# Programmer.net
KiCad netlist of a schematic drawn in Altium Designer
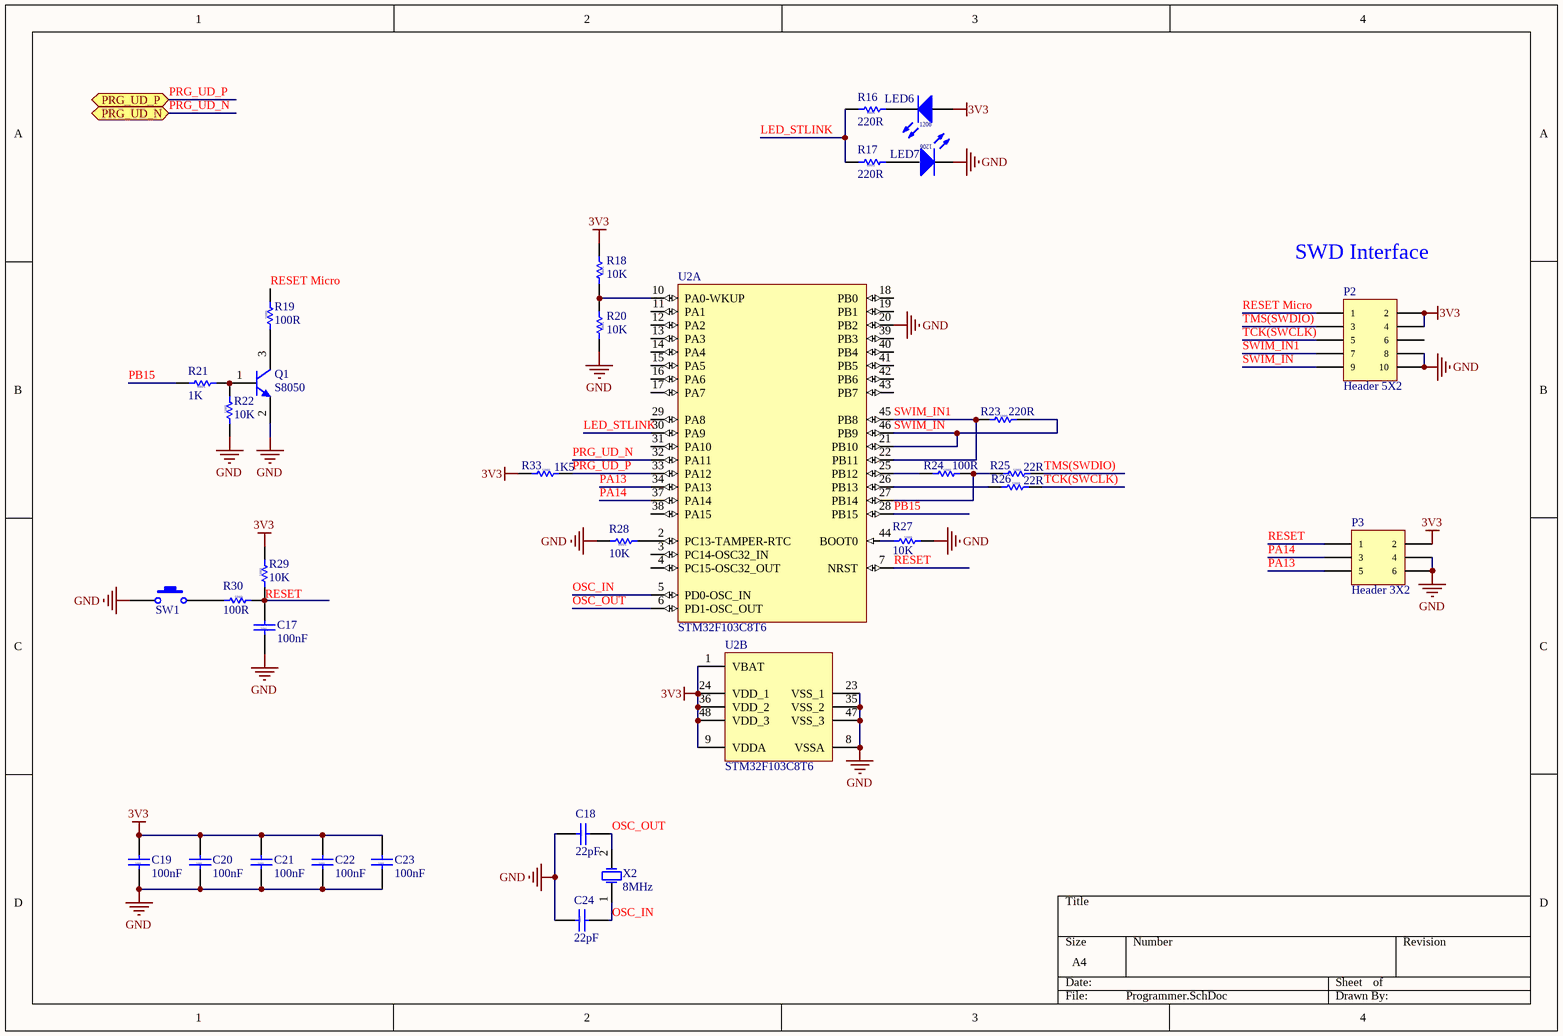
[diagram p0: Programmer.SchDoc]

(export (version "E")
  (design (tool "Eeschema 10.0.6"))
  (components
    (comp (ref "C17")
      (value "100nF")
      (footprint "RES 0805")
      (libsource (lib "Full lib F.kh-V2") (part "CAP 0805"))
    )
    (comp (ref "C18")
      (value "22pF")
      (footprint "RES 0805")
      (libsource (lib "Full lib F.kh-V2") (part "CAP 0805"))
    )
    (comp (ref "C19")
      (value "100nF")
      (footprint "RES 0805")
      (libsource (lib "Full lib F.kh-V2") (part "CAP 0805"))
    )
    (comp (ref "C20")
      (value "100nF")
      (footprint "RES 0805")
      (libsource (lib "Full lib F.kh-V2") (part "CAP 0805"))
    )
    (comp (ref "C21")
      (value "100nF")
      (footprint "RES 0805")
      (libsource (lib "Full lib F.kh-V2") (part "CAP 0805"))
    )
    (comp (ref "C22")
      (value "100nF")
      (footprint "RES 0805")
      (libsource (lib "Full lib F.kh-V2") (part "CAP 0805"))
    )
    (comp (ref "C23")
      (value "100nF")
      (footprint "RES 0805")
      (libsource (lib "Full lib F.kh-V2") (part "CAP 0805"))
    )
    (comp (ref "C24")
      (value "22pF")
      (footprint "RES 0805")
      (libsource (lib "Full lib F.kh-V2") (part "CAP 0805"))
    )
    (comp (ref "LED6")
      (value "LED 1206")
      (footprint "LED 1206")
      (libsource (lib "Full lib F.kh-V2") (part "LED 1206"))
    )
    (comp (ref "LED7")
      (value "LED 1206")
      (footprint "LED 1206")
      (libsource (lib "Full lib F.kh-V2") (part "LED 1206"))
    )
    (comp (ref "P2")
      (value "Header 5X2")
      (footprint "HDR2X5")
      (description "Header, 5-Pin, Dual row")
      (fields (field (name "PUBLISHER") "Altium Limited"))
      (libsource (lib "Full lib F.kh-V2") (part "Header 5X2"))
    )
    (comp (ref "P3")
      (value "Header 3X2")
      (footprint "HDR2X3")
      (description "Header, 3-Pin, Dual row")
      (fields (field (name "PUBLISHER") "Altium Limited"))
      (libsource (lib "Full lib F.kh-V2") (part "Header 3X2"))
    )
    (comp (ref "Q1")
      (value "S8050")
      (footprint "SOT-23")
      (libsource (lib "Full lib F.kh-V2") (part "S8050 SMD"))
    )
    (comp (ref "R16")
      (value "220R")
      (footprint "RES 0805")
      (libsource (lib "Full lib F.kh-V2") (part "RES 0805"))
    )
    (comp (ref "R17")
      (value "220R")
      (footprint "RES 0805")
      (libsource (lib "Full lib F.kh-V2") (part "RES 0805"))
    )
    (comp (ref "R18")
      (value "10K")
      (footprint "RES 0805")
      (libsource (lib "Full lib F.kh-V2") (part "RES 0805"))
    )
    (comp (ref "R19")
      (value "100R")
      (footprint "RES 0805")
      (libsource (lib "Full lib F.kh-V2") (part "RES 0805"))
    )
    (comp (ref "R20")
      (value "10K")
      (footprint "RES 0805")
      (libsource (lib "Full lib F.kh-V2") (part "RES 0805"))
    )
    (comp (ref "R21")
      (value "1K")
      (footprint "RES 0805")
      (libsource (lib "Full lib F.kh-V2") (part "RES 0805"))
    )
    (comp (ref "R22")
      (value "10K")
      (footprint "RES 0805")
      (libsource (lib "Full lib F.kh-V2") (part "RES 0805"))
    )
    (comp (ref "R23")
      (value "220R")
      (footprint "RES 0805")
      (libsource (lib "Full lib F.kh-V2") (part "RES 0805"))
    )
    (comp (ref "R24")
      (value "100R")
      (footprint "RES 0805")
      (libsource (lib "Full lib F.kh-V2") (part "RES 0805"))
    )
    (comp (ref "R25")
      (value "22R")
      (footprint "RES 0805")
      (libsource (lib "Full lib F.kh-V2") (part "RES 0805"))
    )
    (comp (ref "R26")
      (value "22R")
      (footprint "RES 0805")
      (libsource (lib "Full lib F.kh-V2") (part "RES 0805"))
    )
    (comp (ref "R27")
      (value "10K")
      (footprint "RES 0805")
      (libsource (lib "Full lib F.kh-V2") (part "RES 0805"))
    )
    (comp (ref "R28")
      (value "10K")
      (footprint "RES 0805")
      (libsource (lib "Full lib F.kh-V2") (part "RES 0805"))
    )
    (comp (ref "R29")
      (value "10K")
      (footprint "RES 0805")
      (libsource (lib "Full lib F.kh-V2") (part "RES 0805"))
    )
    (comp (ref "R30")
      (value "100R")
      (footprint "RES 0805")
      (libsource (lib "Full lib F.kh-V2") (part "RES 0805"))
    )
    (comp (ref "R33")
      (value "1K5")
      (footprint "RES 0805")
      (libsource (lib "Full lib F.kh-V2") (part "RES 0805"))
    )
    (comp (ref "SW1")
      (value "Pushing Switch")
      (footprint "micro sch")
      (fields (field (name "PUBLISHER") "Altium Limited"))
      (libsource (lib "Full lib F.kh-V2") (part "Pushing Switch 2Pin"))
    )
    (comp (ref "U2")
      (value "STM32F103C8T6")
      (footprint "STM-LQFP48_N")
      (libsource (lib "STMicroelectronics STM32 F1") (part "STM32F103C8T6"))
    )
    (comp (ref "X2")
      (value "8MHz")
      (footprint "XTAL - SMD")
      (libsource (lib "Full lib F.kh-V2") (part "XTAL - SMD"))
    )
  )
  (nets
    (net (code "1") (name "/LED_STLINK") (class "Default")
      (node (ref "R16") (pin "2") (pinfunction "2_2") (pintype "passive"))
      (node (ref "R17") (pin "2") (pinfunction "2_2") (pintype "passive"))
      (node (ref "U2") (pin "30") (pinfunction "PA9_30") (pintype "bidirectional"))
    )
    (net (code "2") (name "/OSC_IN") (class "Default")
      (node (ref "C24") (pin "2") (pinfunction "2_2") (pintype "passive"))
      (node (ref "U2") (pin "5") (pinfunction "PD0-OSC_IN_5") (pintype "bidirectional"))
      (node (ref "X2") (pin "1") (pinfunction "OSC1_1") (pintype "passive"))
    )
    (net (code "3") (name "/OSC_OUT") (class "Default")
      (node (ref "C18") (pin "2") (pinfunction "2_2") (pintype "passive"))
      (node (ref "U2") (pin "6") (pinfunction "PD1-OSC_OUT_6") (pintype "bidirectional"))
      (node (ref "X2") (pin "2") (pinfunction "OSC2_2") (pintype "passive"))
    )
    (net (code "4") (name "/PA13") (class "Default")
      (node (ref "P3") (pin "5") (pinfunction "5_5") (pintype "passive"))
      (node (ref "U2") (pin "34") (pinfunction "PA13_34") (pintype "bidirectional"))
    )
    (net (code "5") (name "/PA14") (class "Default")
      (node (ref "P3") (pin "3") (pinfunction "3_3") (pintype "passive"))
      (node (ref "U2") (pin "37") (pinfunction "PA14_37") (pintype "bidirectional"))
    )
    (net (code "6") (name "/PB15") (class "Default")
      (node (ref "R21") (pin "2") (pinfunction "2_2") (pintype "passive"))
      (node (ref "U2") (pin "28") (pinfunction "PB15_28") (pintype "bidirectional"))
    )
    (net (code "7") (name "/PRG_UD_N") (class "Default")
      (node (ref "U2") (pin "32") (pinfunction "PA11_32") (pintype "bidirectional"))
    )
    (net (code "8") (name "/PRG_UD_P") (class "Default")
      (node (ref "R33") (pin "2") (pinfunction "2_2") (pintype "passive"))
      (node (ref "U2") (pin "33") (pinfunction "PA12_33") (pintype "bidirectional"))
    )
    (net (code "9") (name "/RESET") (class "Default")
      (node (ref "C17") (pin "2") (pinfunction "2_2") (pintype "passive"))
      (node (ref "P3") (pin "1") (pinfunction "1_1") (pintype "passive"))
      (node (ref "R29") (pin "1") (pinfunction "1_1") (pintype "passive"))
      (node (ref "R30") (pin "2") (pinfunction "2_2") (pintype "passive"))
      (node (ref "U2") (pin "7") (pinfunction "NRST_7") (pintype "bidirectional"))
    )
    (net (code "10") (name "/RESET Micro") (class "Default")
      (node (ref "P2") (pin "1") (pinfunction "1_1") (pintype "passive"))
      (node (ref "R19") (pin "2") (pinfunction "2_2") (pintype "passive"))
    )
    (net (code "11") (name "/SWIM_IN") (class "Default")
      (node (ref "P2") (pin "9") (pinfunction "9_9") (pintype "passive"))
      (node (ref "R23") (pin "2") (pinfunction "2_2") (pintype "passive"))
      (node (ref "U2") (pin "21") (pinfunction "PB10_21") (pintype "bidirectional"))
      (node (ref "U2") (pin "46") (pinfunction "PB9_46") (pintype "bidirectional"))
    )
    (net (code "12") (name "/SWIM_IN1") (class "Default")
      (node (ref "P2") (pin "7") (pinfunction "7_7") (pintype "passive"))
      (node (ref "R23") (pin "1") (pinfunction "1_1") (pintype "passive"))
      (node (ref "U2") (pin "22") (pinfunction "PB11_22") (pintype "bidirectional"))
      (node (ref "U2") (pin "45") (pinfunction "PB8_45") (pintype "bidirectional"))
    )
    (net (code "13") (name "/TCK(SWCLK)") (class "Default")
      (node (ref "P2") (pin "5") (pinfunction "5_5") (pintype "passive"))
      (node (ref "R26") (pin "2") (pinfunction "2_2") (pintype "passive"))
    )
    (net (code "14") (name "/TMS(SWDIO)") (class "Default")
      (node (ref "P2") (pin "3") (pinfunction "3_3") (pintype "passive"))
      (node (ref "R25") (pin "2") (pinfunction "2_2") (pintype "passive"))
    )
    (net (code "15") (name "3V3") (class "Default")
      (node (ref "C19") (pin "2") (pinfunction "2_2") (pintype "passive"))
      (node (ref "C20") (pin "2") (pinfunction "2_2") (pintype "passive"))
      (node (ref "C21") (pin "2") (pinfunction "2_2") (pintype "passive"))
      (node (ref "C22") (pin "2") (pinfunction "2_2") (pintype "passive"))
      (node (ref "C23") (pin "2") (pinfunction "2_2") (pintype "passive"))
      (node (ref "LED6") (pin "1") (pinfunction "A_1") (pintype "passive"))
      (node (ref "P2") (pin "2") (pinfunction "2_2") (pintype "passive"))
      (node (ref "P2") (pin "4") (pinfunction "4_4") (pintype "passive"))
      (node (ref "P3") (pin "2") (pinfunction "2_2") (pintype "passive"))
      (node (ref "R18") (pin "1") (pinfunction "1_1") (pintype "passive"))
      (node (ref "R29") (pin "2") (pinfunction "2_2") (pintype "passive"))
      (node (ref "R33") (pin "1") (pinfunction "1_1") (pintype "passive"))
      (node (ref "U2") (pin "1") (pinfunction "VBAT_1") (pintype "power_in"))
      (node (ref "U2") (pin "24") (pinfunction "VDD_1_24") (pintype "power_in"))
      (node (ref "U2") (pin "36") (pinfunction "VDD_2_36") (pintype "power_in"))
      (node (ref "U2") (pin "48") (pinfunction "VDD_3_48") (pintype "power_in"))
      (node (ref "U2") (pin "9") (pinfunction "VDDA_9") (pintype "power_in"))
    )
    (net (code "16") (name "GND") (class "Default")
      (node (ref "C17") (pin "1") (pinfunction "1_1") (pintype "passive"))
      (node (ref "C18") (pin "1") (pinfunction "1_1") (pintype "passive"))
      (node (ref "C19") (pin "1") (pinfunction "1_1") (pintype "passive"))
      (node (ref "C20") (pin "1") (pinfunction "1_1") (pintype "passive"))
      (node (ref "C21") (pin "1") (pinfunction "1_1") (pintype "passive"))
      (node (ref "C22") (pin "1") (pinfunction "1_1") (pintype "passive"))
      (node (ref "C23") (pin "1") (pinfunction "1_1") (pintype "passive"))
      (node (ref "C24") (pin "1") (pinfunction "1_1") (pintype "passive"))
      (node (ref "LED7") (pin "2") (pinfunction "K_2") (pintype "passive"))
      (node (ref "P2") (pin "10") (pinfunction "10_10") (pintype "passive"))
      (node (ref "P2") (pin "8") (pinfunction "8_8") (pintype "passive"))
      (node (ref "P3") (pin "4") (pinfunction "4_4") (pintype "passive"))
      (node (ref "P3") (pin "6") (pinfunction "6_6") (pintype "passive"))
      (node (ref "Q1") (pin "2") (pinfunction "E_2") (pintype "passive"))
      (node (ref "R20") (pin "2") (pinfunction "2_2") (pintype "passive"))
      (node (ref "R22") (pin "1") (pinfunction "1_1") (pintype "passive"))
      (node (ref "R27") (pin "2") (pinfunction "2_2") (pintype "passive"))
      (node (ref "R28") (pin "2") (pinfunction "2_2") (pintype "passive"))
      (node (ref "SW1") (pin "1") (pinfunction "1_1") (pintype "passive"))
      (node (ref "U2") (pin "20") (pinfunction "PB2_20") (pintype "bidirectional"))
      (node (ref "U2") (pin "23") (pinfunction "VSS_1_23") (pintype "power_in"))
      (node (ref "U2") (pin "35") (pinfunction "VSS_2_35") (pintype "power_in"))
      (node (ref "U2") (pin "47") (pinfunction "VSS_3_47") (pintype "power_in"))
      (node (ref "U2") (pin "8") (pinfunction "VSSA_8") (pintype "power_in"))
    )
    (net (code "17") (name "Net-(LED6-K)") (class "Default")
      (node (ref "LED6") (pin "2") (pinfunction "K_2") (pintype "passive"))
      (node (ref "R16") (pin "1") (pinfunction "1_1") (pintype "passive"))
    )
    (net (code "18") (name "Net-(LED7-A)") (class "Default")
      (node (ref "LED7") (pin "1") (pinfunction "A_1") (pintype "passive"))
      (node (ref "R17") (pin "1") (pinfunction "1_1") (pintype "passive"))
    )
    (net (code "19") (name "Net-(Q1-B)") (class "Default")
      (node (ref "Q1") (pin "1") (pinfunction "B_1") (pintype "passive"))
      (node (ref "R21") (pin "1") (pinfunction "1_1") (pintype "passive"))
      (node (ref "R22") (pin "2") (pinfunction "2_2") (pintype "passive"))
    )
    (net (code "20") (name "Net-(Q1-C)") (class "Default")
      (node (ref "Q1") (pin "3") (pinfunction "C_3") (pintype "passive"))
      (node (ref "R19") (pin "1") (pinfunction "1_1") (pintype "passive"))
    )
    (net (code "21") (name "Net-(R30-Pad1)") (class "Default")
      (node (ref "R30") (pin "1") (pinfunction "1_1") (pintype "passive"))
      (node (ref "SW1") (pin "2") (pinfunction "2_2") (pintype "passive"))
    )
    (net (code "22") (name "Net-(U2A-BOOT0)") (class "Default")
      (node (ref "R27") (pin "1") (pinfunction "1_1") (pintype "passive"))
      (node (ref "U2") (pin "44") (pinfunction "BOOT0_44") (pintype "input"))
    )
    (net (code "23") (name "Net-(U2A-PA0-WKUP)") (class "Default")
      (node (ref "R18") (pin "2") (pinfunction "2_2") (pintype "passive"))
      (node (ref "R20") (pin "1") (pinfunction "1_1") (pintype "passive"))
      (node (ref "U2") (pin "10") (pinfunction "PA0-WKUP_10") (pintype "bidirectional"))
    )
    (net (code "24") (name "Net-(U2A-PB12)") (class "Default")
      (node (ref "R24") (pin "1") (pinfunction "1_1") (pintype "passive"))
      (node (ref "U2") (pin "25") (pinfunction "PB12_25") (pintype "bidirectional"))
    )
    (net (code "25") (name "Net-(U2A-PB13)") (class "Default")
      (node (ref "R26") (pin "1") (pinfunction "1_1") (pintype "passive"))
      (node (ref "U2") (pin "26") (pinfunction "PB13_26") (pintype "bidirectional"))
    )
    (net (code "26") (name "Net-(U2A-PB14)") (class "Default")
      (node (ref "R24") (pin "2") (pinfunction "2_2") (pintype "passive"))
      (node (ref "R25") (pin "1") (pinfunction "1_1") (pintype "passive"))
      (node (ref "U2") (pin "27") (pinfunction "PB14_27") (pintype "bidirectional"))
    )
    (net (code "27") (name "Net-(U2A-PC13-TAMPER-RTC)") (class "Default")
      (node (ref "R28") (pin "1") (pinfunction "1_1") (pintype "passive"))
      (node (ref "U2") (pin "2") (pinfunction "PC13-TAMPER-RTC_2") (pintype "bidirectional"))
    )
    (net (code "28") (name "unconnected-(P2-Pad6)") (class "Default")
      (node (ref "P2") (pin "6") (pinfunction "6_6") (pintype "passive"))
    )
    (net (code "29") (name "unconnected-(U2A-PA1-Pad11)") (class "Default")
      (node (ref "U2") (pin "11") (pinfunction "PA1_11") (pintype "bidirectional"))
    )
    (net (code "30") (name "unconnected-(U2A-PA2-Pad12)") (class "Default")
      (node (ref "U2") (pin "12") (pinfunction "PA2_12") (pintype "bidirectional"))
    )
    (net (code "31") (name "unconnected-(U2A-PA3-Pad13)") (class "Default")
      (node (ref "U2") (pin "13") (pinfunction "PA3_13") (pintype "bidirectional"))
    )
    (net (code "32") (name "unconnected-(U2A-PA4-Pad14)") (class "Default")
      (node (ref "U2") (pin "14") (pinfunction "PA4_14") (pintype "bidirectional"))
    )
    (net (code "33") (name "unconnected-(U2A-PA5-Pad15)") (class "Default")
      (node (ref "U2") (pin "15") (pinfunction "PA5_15") (pintype "bidirectional"))
    )
    (net (code "34") (name "unconnected-(U2A-PA6-Pad16)") (class "Default")
      (node (ref "U2") (pin "16") (pinfunction "PA6_16") (pintype "bidirectional"))
    )
    (net (code "35") (name "unconnected-(U2A-PA7-Pad17)") (class "Default")
      (node (ref "U2") (pin "17") (pinfunction "PA7_17") (pintype "bidirectional"))
    )
    (net (code "36") (name "unconnected-(U2A-PA8-Pad29)") (class "Default")
      (node (ref "U2") (pin "29") (pinfunction "PA8_29") (pintype "bidirectional"))
    )
    (net (code "37") (name "unconnected-(U2A-PA10-Pad31)") (class "Default")
      (node (ref "U2") (pin "31") (pinfunction "PA10_31") (pintype "bidirectional"))
    )
    (net (code "38") (name "unconnected-(U2A-PA15-Pad38)") (class "Default")
      (node (ref "U2") (pin "38") (pinfunction "PA15_38") (pintype "bidirectional"))
    )
    (net (code "39") (name "unconnected-(U2A-PB0-Pad18)") (class "Default")
      (node (ref "U2") (pin "18") (pinfunction "PB0_18") (pintype "bidirectional"))
    )
    (net (code "40") (name "unconnected-(U2A-PB1-Pad19)") (class "Default")
      (node (ref "U2") (pin "19") (pinfunction "PB1_19") (pintype "bidirectional"))
    )
    (net (code "41") (name "unconnected-(U2A-PB3-Pad39)") (class "Default")
      (node (ref "U2") (pin "39") (pinfunction "PB3_39") (pintype "bidirectional"))
    )
    (net (code "42") (name "unconnected-(U2A-PB4-Pad40)") (class "Default")
      (node (ref "U2") (pin "40") (pinfunction "PB4_40") (pintype "bidirectional"))
    )
    (net (code "43") (name "unconnected-(U2A-PB5-Pad41)") (class "Default")
      (node (ref "U2") (pin "41") (pinfunction "PB5_41") (pintype "bidirectional"))
    )
    (net (code "44") (name "unconnected-(U2A-PB6-Pad42)") (class "Default")
      (node (ref "U2") (pin "42") (pinfunction "PB6_42") (pintype "bidirectional"))
    )
    (net (code "45") (name "unconnected-(U2A-PB7-Pad43)") (class "Default")
      (node (ref "U2") (pin "43") (pinfunction "PB7_43") (pintype "bidirectional"))
    )
    (net (code "46") (name "unconnected-(U2A-PC14-OSC32_IN-Pad3)") (class "Default")
      (node (ref "U2") (pin "3") (pinfunction "PC14-OSC32_IN_3") (pintype "bidirectional"))
    )
    (net (code "47") (name "unconnected-(U2A-PC15-OSC32_OUT-Pad4)") (class "Default")
      (node (ref "U2") (pin "4") (pinfunction "PC15-OSC32_OUT_4") (pintype "bidirectional"))
    )
  )
)
